# JTAG.net
KiCad netlist of a schematic drawn in Altium Designer
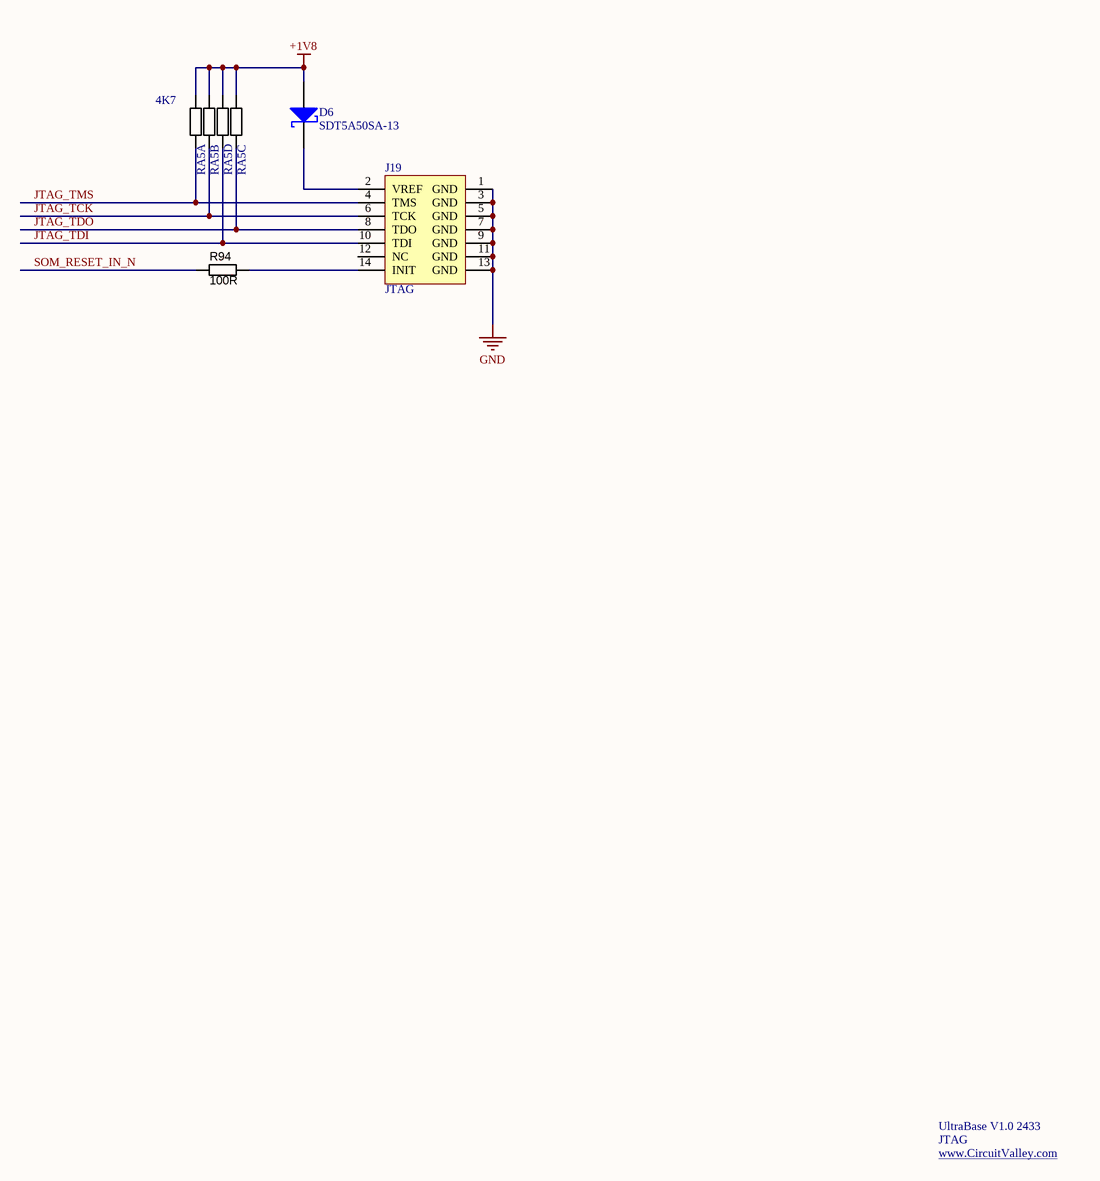
[diagram p0: JTAG.SchDoc]

(export (version "E")
  (design (tool "Eeschema 10.0.6"))
  (components
    (comp (ref "D6")
      (value "SDT5A50SA-13")
      (footprint "DO-214AC")
      (description "Diode")
      (libsource (lib "cvlib") (part "Diode"))
    )
    (comp (ref "J19") (value "JTAG") (footprint "878321420") (libsource (lib "cvlib") (part "Xilinx_JTAG")))
    (comp (ref "R94")
      (value "100R")
      (footprint "RESC1608N")
      (description "Resistor, SMD chip")
      (fields (field (name "TOLERANCE") "±5%") (field (name "Comment") "RES_NL_0603"))
      (libsource (lib "PBL - Resistors") (part "RES_NL_0603"))
    )
    (comp (ref "RA5")
      (value "Thick Film")
      (footprint "YC164")
      (description "Resistor array 4-pack 5% 0402 SMD")
      (libsource (lib "cvlib") (part "RES_ARRAY_0402_5%"))
    )
  )
  (nets
    (net (code "1") (name "+1V8") (class "Default")
      (node (ref "D6") (pin "1") (pinfunction "A_1") (pintype "passive"))
      (node (ref "RA5") (pin "5") (pinfunction "5_5") (pintype "passive"))
      (node (ref "RA5") (pin "6") (pinfunction "6_6") (pintype "passive"))
      (node (ref "RA5") (pin "7") (pinfunction "7_7") (pintype "passive"))
      (node (ref "RA5") (pin "8") (pinfunction "8_8") (pintype "passive"))
    )
    (net (code "2") (name "/JTAG_TCK") (class "Default")
      (node (ref "J19") (pin "6") (pinfunction "TCK_6") (pintype "passive"))
      (node (ref "RA5") (pin "2") (pinfunction "2_2") (pintype "passive"))
    )
    (net (code "3") (name "/JTAG_TDI") (class "Default")
      (node (ref "J19") (pin "10") (pinfunction "TDI_10") (pintype "passive"))
      (node (ref "RA5") (pin "4") (pinfunction "4_4") (pintype "passive"))
    )
    (net (code "4") (name "/JTAG_TDO") (class "Default")
      (node (ref "J19") (pin "8") (pinfunction "TDO_8") (pintype "passive"))
      (node (ref "RA5") (pin "3") (pinfunction "3_3") (pintype "passive"))
    )
    (net (code "5") (name "/JTAG_TMS") (class "Default")
      (node (ref "J19") (pin "4") (pinfunction "TMS_4") (pintype "passive"))
      (node (ref "RA5") (pin "1") (pinfunction "1_1") (pintype "passive"))
    )
    (net (code "6") (name "/SOM_RESET_IN_N") (class "Default")
      (node (ref "R94") (pin "2") (pinfunction "2_2") (pintype "passive"))
    )
    (net (code "7") (name "GND") (class "Default")
      (node (ref "J19") (pin "1") (pinfunction "GND_1") (pintype "passive"))
      (node (ref "J19") (pin "11") (pinfunction "GND_11") (pintype "passive"))
      (node (ref "J19") (pin "13") (pinfunction "GND_13") (pintype "passive"))
      (node (ref "J19") (pin "3") (pinfunction "GND_3") (pintype "passive"))
      (node (ref "J19") (pin "5") (pinfunction "GND_5") (pintype "passive"))
      (node (ref "J19") (pin "7") (pinfunction "GND_7") (pintype "passive"))
      (node (ref "J19") (pin "9") (pinfunction "GND_9") (pintype "passive"))
    )
    (net (code "8") (name "Net-(D6-K)") (class "Default")
      (node (ref "D6") (pin "2") (pinfunction "K_2") (pintype "passive"))
      (node (ref "J19") (pin "2") (pinfunction "VREF_2") (pintype "passive"))
    )
    (net (code "9") (name "Net-(J19-INIT)") (class "Default")
      (node (ref "J19") (pin "14") (pinfunction "INIT_14") (pintype "passive"))
      (node (ref "R94") (pin "1") (pinfunction "1_1") (pintype "passive"))
    )
    (net (code "10") (name "unconnected-(J19-NC-Pad12)") (class "Default")
      (node (ref "J19") (pin "12") (pinfunction "NC_12") (pintype "passive"))
    )
  )
)
